# EXT_ADIN.net
KiCad netlist of a schematic drawn in EAGLE
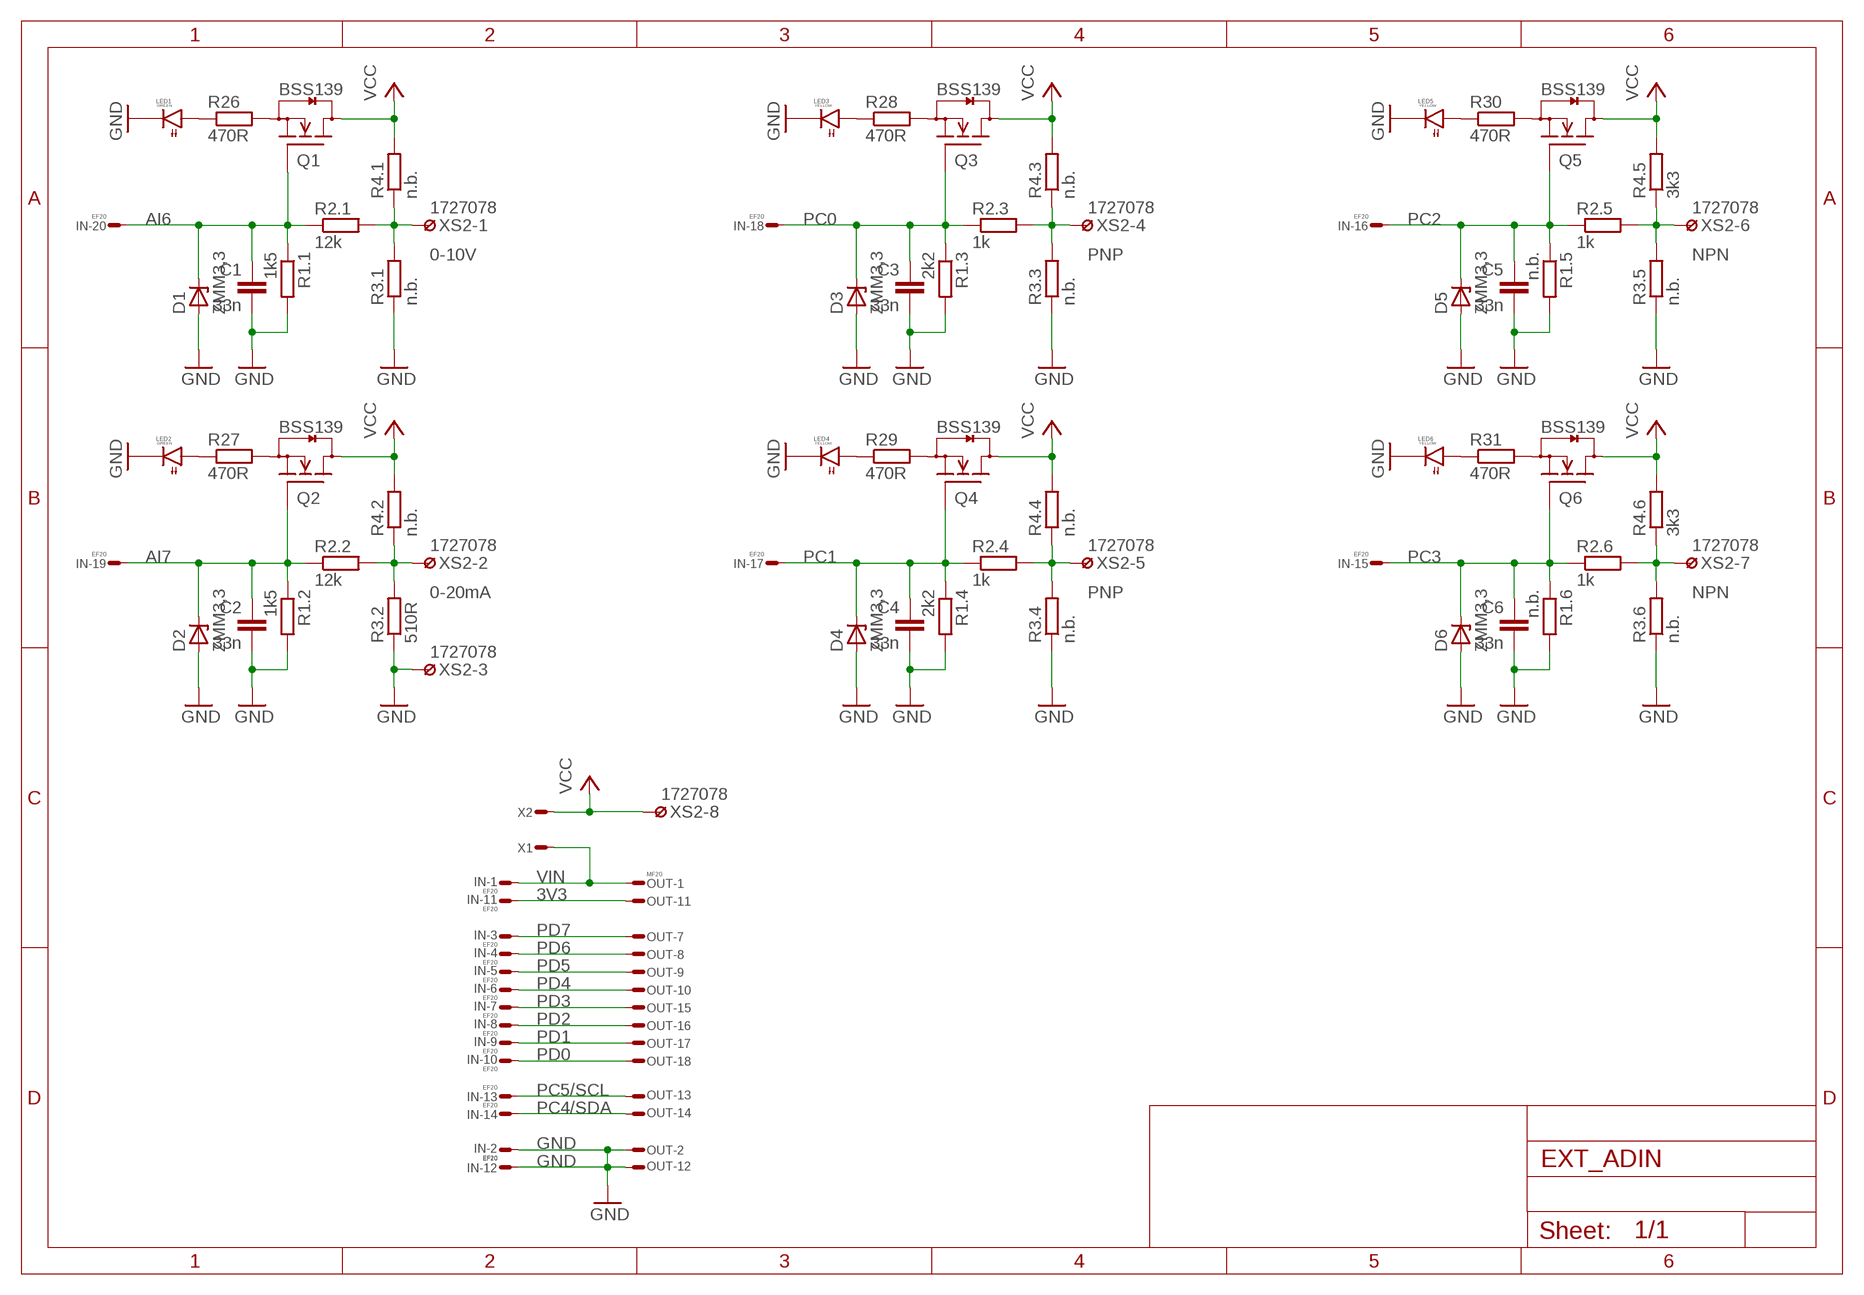
[diagram p0: schematic, sheet 1]

(export (version "E")
  (design (tool "Eeschema 10.0.6"))
  (components
    (comp (ref "C1")
      (value "33n")
      (footprint "eagle-import:1206")
      (libsource (lib "eagle-import") (part "C1206"))
    )
    (comp (ref "C2")
      (value "33n")
      (footprint "eagle-import:1206")
      (libsource (lib "eagle-import") (part "C1206"))
    )
    (comp (ref "C3")
      (value "33n")
      (footprint "eagle-import:1206")
      (libsource (lib "eagle-import") (part "C1206"))
    )
    (comp (ref "C4")
      (value "33n")
      (footprint "eagle-import:1206")
      (libsource (lib "eagle-import") (part "C1206"))
    )
    (comp (ref "C5")
      (value "33n")
      (footprint "eagle-import:1206")
      (libsource (lib "eagle-import") (part "C1206"))
    )
    (comp (ref "C6")
      (value "33n")
      (footprint "eagle-import:1206")
      (libsource (lib "eagle-import") (part "C1206"))
    )
    (comp (ref "D1")
      (value "ZMM3,3")
      (footprint "eagle-import:SOD80")
      (libsource (lib "eagle-import") (part "ZDSOD80"))
    )
    (comp (ref "D2")
      (value "ZMM3,3")
      (footprint "eagle-import:SOD80")
      (libsource (lib "eagle-import") (part "ZDSOD80"))
    )
    (comp (ref "D3")
      (value "ZMM3,3")
      (footprint "eagle-import:SOD80")
      (libsource (lib "eagle-import") (part "ZDSOD80"))
    )
    (comp (ref "D4")
      (value "ZMM3,3")
      (footprint "eagle-import:SOD80")
      (libsource (lib "eagle-import") (part "ZDSOD80"))
    )
    (comp (ref "D5")
      (value "ZMM3,3")
      (footprint "eagle-import:SOD80")
      (libsource (lib "eagle-import") (part "ZDSOD80"))
    )
    (comp (ref "D6")
      (value "ZMM3,3")
      (footprint "eagle-import:SOD80")
      (libsource (lib "eagle-import") (part "ZDSOD80"))
    )
    (comp (ref "IN")
      (value "EF20")
      (footprint "eagle-import:FE10-2WSS")
      (libsource (lib "eagle-import") (part "FE20ELSS"))
    )
    (comp (ref "LED1")
      (value "GREEN")
      (footprint "eagle-import:1206")
      (libsource (lib "eagle-import") (part "LED1206"))
    )
    (comp (ref "LED2")
      (value "GREEN")
      (footprint "eagle-import:1206")
      (libsource (lib "eagle-import") (part "LED1206"))
    )
    (comp (ref "LED3")
      (value "YELLOW")
      (footprint "eagle-import:1206")
      (libsource (lib "eagle-import") (part "LED1206"))
    )
    (comp (ref "LED4")
      (value "YELLOW")
      (footprint "eagle-import:1206")
      (libsource (lib "eagle-import") (part "LED1206"))
    )
    (comp (ref "LED5")
      (value "YELLOW")
      (footprint "eagle-import:1206")
      (libsource (lib "eagle-import") (part "LED1206"))
    )
    (comp (ref "LED6")
      (value "YELLOW")
      (footprint "eagle-import:1206")
      (libsource (lib "eagle-import") (part "LED1206"))
    )
    (comp (ref "OUT")
      (value "MF20")
      (footprint "eagle-import:ML20LS")
      (libsource (lib "eagle-import") (part "ML20?ELS"))
    )
    (comp (ref "Q1")
      (value "BSS139")
      (footprint "eagle-import:SOT23")
      (libsource (lib "eagle-import") (part "FET-ND23"))
    )
    (comp (ref "Q2")
      (value "BSS139")
      (footprint "eagle-import:SOT23")
      (libsource (lib "eagle-import") (part "FET-ND23"))
    )
    (comp (ref "Q3")
      (value "BSS139")
      (footprint "eagle-import:SOT23")
      (libsource (lib "eagle-import") (part "FET-ND23"))
    )
    (comp (ref "Q4")
      (value "BSS139")
      (footprint "eagle-import:SOT23")
      (libsource (lib "eagle-import") (part "FET-ND23"))
    )
    (comp (ref "Q5")
      (value "BSS139")
      (footprint "eagle-import:SOT23")
      (libsource (lib "eagle-import") (part "FET-ND23"))
    )
    (comp (ref "Q6")
      (value "BSS139")
      (footprint "eagle-import:SOT23")
      (libsource (lib "eagle-import") (part "FET-ND23"))
    )
    (comp (ref "R1.1")
      (value "1k5")
      (footprint "eagle-import:1206")
      (libsource (lib "eagle-import") (part "R1206"))
    )
    (comp (ref "R1.2")
      (value "1k5")
      (footprint "eagle-import:1206")
      (libsource (lib "eagle-import") (part "R1206"))
    )
    (comp (ref "R1.3")
      (value "2k2")
      (footprint "eagle-import:1206")
      (libsource (lib "eagle-import") (part "R1206"))
    )
    (comp (ref "R1.4")
      (value "2k2")
      (footprint "eagle-import:1206")
      (libsource (lib "eagle-import") (part "R1206"))
    )
    (comp (ref "R1.5")
      (value "n.b.")
      (footprint "eagle-import:1206")
      (libsource (lib "eagle-import") (part "R1206"))
    )
    (comp (ref "R1.6")
      (value "n.b.")
      (footprint "eagle-import:1206")
      (libsource (lib "eagle-import") (part "R1206"))
    )
    (comp (ref "R2.1")
      (value "12k")
      (footprint "eagle-import:1206")
      (libsource (lib "eagle-import") (part "R1206"))
    )
    (comp (ref "R2.2")
      (value "12k")
      (footprint "eagle-import:1206")
      (libsource (lib "eagle-import") (part "R1206"))
    )
    (comp (ref "R2.3")
      (value "1k")
      (footprint "eagle-import:1206")
      (libsource (lib "eagle-import") (part "R1206"))
    )
    (comp (ref "R2.4")
      (value "1k")
      (footprint "eagle-import:1206")
      (libsource (lib "eagle-import") (part "R1206"))
    )
    (comp (ref "R2.5")
      (value "1k")
      (footprint "eagle-import:1206")
      (libsource (lib "eagle-import") (part "R1206"))
    )
    (comp (ref "R2.6")
      (value "1k")
      (footprint "eagle-import:1206")
      (libsource (lib "eagle-import") (part "R1206"))
    )
    (comp (ref "R3.1")
      (value "n.b.")
      (footprint "eagle-import:1206")
      (libsource (lib "eagle-import") (part "R1206"))
    )
    (comp (ref "R3.2")
      (value "510R")
      (footprint "eagle-import:1206")
      (libsource (lib "eagle-import") (part "R1206"))
    )
    (comp (ref "R3.3")
      (value "n.b.")
      (footprint "eagle-import:1206")
      (libsource (lib "eagle-import") (part "R1206"))
    )
    (comp (ref "R3.4")
      (value "n.b.")
      (footprint "eagle-import:1206")
      (libsource (lib "eagle-import") (part "R1206"))
    )
    (comp (ref "R3.5")
      (value "n.b.")
      (footprint "eagle-import:1206")
      (libsource (lib "eagle-import") (part "R1206"))
    )
    (comp (ref "R3.6")
      (value "n.b.")
      (footprint "eagle-import:1206")
      (libsource (lib "eagle-import") (part "R1206"))
    )
    (comp (ref "R4.1")
      (value "n.b.")
      (footprint "eagle-import:1206")
      (libsource (lib "eagle-import") (part "R1206"))
    )
    (comp (ref "R4.2")
      (value "n.b.")
      (footprint "eagle-import:1206")
      (libsource (lib "eagle-import") (part "R1206"))
    )
    (comp (ref "R4.3")
      (value "n.b.")
      (footprint "eagle-import:1206")
      (libsource (lib "eagle-import") (part "R1206"))
    )
    (comp (ref "R4.4")
      (value "n.b.")
      (footprint "eagle-import:1206")
      (libsource (lib "eagle-import") (part "R1206"))
    )
    (comp (ref "R4.5")
      (value "3k3")
      (footprint "eagle-import:1206")
      (libsource (lib "eagle-import") (part "R1206"))
    )
    (comp (ref "R4.6")
      (value "3k3")
      (footprint "eagle-import:1206")
      (libsource (lib "eagle-import") (part "R1206"))
    )
    (comp (ref "R26")
      (value "470R")
      (footprint "eagle-import:1206")
      (libsource (lib "eagle-import") (part "R1206"))
    )
    (comp (ref "R27")
      (value "470R")
      (footprint "eagle-import:1206")
      (libsource (lib "eagle-import") (part "R1206"))
    )
    (comp (ref "R28")
      (value "470R")
      (footprint "eagle-import:1206")
      (libsource (lib "eagle-import") (part "R1206"))
    )
    (comp (ref "R29")
      (value "470R")
      (footprint "eagle-import:1206")
      (libsource (lib "eagle-import") (part "R1206"))
    )
    (comp (ref "R30")
      (value "470R")
      (footprint "eagle-import:1206")
      (libsource (lib "eagle-import") (part "R1206"))
    )
    (comp (ref "R31")
      (value "470R")
      (footprint "eagle-import:1206")
      (libsource (lib "eagle-import") (part "R1206"))
    )
    (comp (ref "X1")
      (value "WIREPADT1.6/0.9")
      (footprint "eagle-import:T1.6_0.9")
      (libsource (lib "eagle-import") (part "WIREPADT1.6/0.9"))
    )
    (comp (ref "X2")
      (value "WIREPADT1.6/0.9")
      (footprint "eagle-import:T1.6_0.9")
      (libsource (lib "eagle-import") (part "WIREPADT1.6/0.9"))
    )
    (comp (ref "XS2")
      (value "1727078")
      (footprint "eagle-import:1727078")
      (libsource (lib "eagle-import") (part "CON8-SS381"))
    )
  )
  (nets
    (net (code "1") (name "/3V3") (class "Default")
      (node (ref "IN") (pin "P$11") (pinfunction "S_P$11") (pintype "passive"))
      (node (ref "OUT") (pin "P$11") (pinfunction "S_P$11") (pintype "passive"))
    )
    (net (code "2") (name "/AI6") (class "Default")
      (node (ref "C1") (pin "1") (pinfunction "1_1") (pintype "passive"))
      (node (ref "D1") (pin "C") (pinfunction "C_C") (pintype "passive"))
      (node (ref "IN") (pin "P$20") (pinfunction "S_P$20") (pintype "passive"))
      (node (ref "Q1") (pin "1") (pinfunction "G_1") (pintype "passive"))
      (node (ref "R1.1") (pin "1") (pinfunction "1_1") (pintype "passive"))
      (node (ref "R2.1") (pin "1") (pinfunction "1_1") (pintype "passive"))
    )
    (net (code "3") (name "/AI7") (class "Default")
      (node (ref "C2") (pin "1") (pinfunction "1_1") (pintype "passive"))
      (node (ref "D2") (pin "C") (pinfunction "C_C") (pintype "passive"))
      (node (ref "IN") (pin "P$19") (pinfunction "S_P$19") (pintype "passive"))
      (node (ref "Q2") (pin "1") (pinfunction "G_1") (pintype "passive"))
      (node (ref "R1.2") (pin "1") (pinfunction "1_1") (pintype "passive"))
      (node (ref "R2.2") (pin "1") (pinfunction "1_1") (pintype "passive"))
    )
    (net (code "4") (name "/PC0") (class "Default")
      (node (ref "C3") (pin "1") (pinfunction "1_1") (pintype "passive"))
      (node (ref "D3") (pin "C") (pinfunction "C_C") (pintype "passive"))
      (node (ref "IN") (pin "P$18") (pinfunction "S_P$18") (pintype "passive"))
      (node (ref "Q3") (pin "1") (pinfunction "G_1") (pintype "passive"))
      (node (ref "R1.3") (pin "1") (pinfunction "1_1") (pintype "passive"))
      (node (ref "R2.3") (pin "1") (pinfunction "1_1") (pintype "passive"))
    )
    (net (code "5") (name "/PC1") (class "Default")
      (node (ref "C4") (pin "1") (pinfunction "1_1") (pintype "passive"))
      (node (ref "D4") (pin "C") (pinfunction "C_C") (pintype "passive"))
      (node (ref "IN") (pin "P$17") (pinfunction "S_P$17") (pintype "passive"))
      (node (ref "Q4") (pin "1") (pinfunction "G_1") (pintype "passive"))
      (node (ref "R1.4") (pin "1") (pinfunction "1_1") (pintype "passive"))
      (node (ref "R2.4") (pin "1") (pinfunction "1_1") (pintype "passive"))
    )
    (net (code "6") (name "/PC2") (class "Default")
      (node (ref "C5") (pin "1") (pinfunction "1_1") (pintype "passive"))
      (node (ref "D5") (pin "C") (pinfunction "C_C") (pintype "passive"))
      (node (ref "IN") (pin "P$16") (pinfunction "S_P$16") (pintype "passive"))
      (node (ref "Q5") (pin "1") (pinfunction "G_1") (pintype "passive"))
      (node (ref "R1.5") (pin "1") (pinfunction "1_1") (pintype "passive"))
      (node (ref "R2.5") (pin "1") (pinfunction "1_1") (pintype "passive"))
    )
    (net (code "7") (name "/PC3") (class "Default")
      (node (ref "C6") (pin "1") (pinfunction "1_1") (pintype "passive"))
      (node (ref "D6") (pin "C") (pinfunction "C_C") (pintype "passive"))
      (node (ref "IN") (pin "P$15") (pinfunction "S_P$15") (pintype "passive"))
      (node (ref "Q6") (pin "1") (pinfunction "G_1") (pintype "passive"))
      (node (ref "R1.6") (pin "1") (pinfunction "1_1") (pintype "passive"))
      (node (ref "R2.6") (pin "1") (pinfunction "1_1") (pintype "passive"))
    )
    (net (code "8") (name "/PC4{slash}SDA") (class "Default")
      (node (ref "IN") (pin "P$14") (pinfunction "S_P$14") (pintype "passive"))
      (node (ref "OUT") (pin "P$14") (pinfunction "S_P$14") (pintype "passive"))
    )
    (net (code "9") (name "/PC5{slash}SCL") (class "Default")
      (node (ref "IN") (pin "P$13") (pinfunction "S_P$13") (pintype "passive"))
      (node (ref "OUT") (pin "P$13") (pinfunction "S_P$13") (pintype "passive"))
    )
    (net (code "10") (name "/PD0") (class "Default")
      (node (ref "IN") (pin "P$10") (pinfunction "S_P$10") (pintype "passive"))
      (node (ref "OUT") (pin "P$18") (pinfunction "S_P$18") (pintype "passive"))
    )
    (net (code "11") (name "/PD1") (class "Default")
      (node (ref "IN") (pin "P$9") (pinfunction "S_P$9") (pintype "passive"))
      (node (ref "OUT") (pin "P$17") (pinfunction "S_P$17") (pintype "passive"))
    )
    (net (code "12") (name "/PD2") (class "Default")
      (node (ref "IN") (pin "P$8") (pinfunction "S_P$8") (pintype "passive"))
      (node (ref "OUT") (pin "P$16") (pinfunction "S_P$16") (pintype "passive"))
    )
    (net (code "13") (name "/PD3") (class "Default")
      (node (ref "IN") (pin "P$7") (pinfunction "S_P$7") (pintype "passive"))
      (node (ref "OUT") (pin "P$15") (pinfunction "S_P$15") (pintype "passive"))
    )
    (net (code "14") (name "/PD4") (class "Default")
      (node (ref "IN") (pin "P$6") (pinfunction "S_P$6") (pintype "passive"))
      (node (ref "OUT") (pin "P$10") (pinfunction "S_P$10") (pintype "passive"))
    )
    (net (code "15") (name "/PD5") (class "Default")
      (node (ref "IN") (pin "P$5") (pinfunction "S_P$5") (pintype "passive"))
      (node (ref "OUT") (pin "P$9") (pinfunction "S_P$9") (pintype "passive"))
    )
    (net (code "16") (name "/PD6") (class "Default")
      (node (ref "IN") (pin "P$4") (pinfunction "S_P$4") (pintype "passive"))
      (node (ref "OUT") (pin "P$8") (pinfunction "S_P$8") (pintype "passive"))
    )
    (net (code "17") (name "/PD7") (class "Default")
      (node (ref "IN") (pin "P$3") (pinfunction "S_P$3") (pintype "passive"))
      (node (ref "OUT") (pin "P$7") (pinfunction "S_P$7") (pintype "passive"))
    )
    (net (code "18") (name "/VIN") (class "Default")
      (node (ref "IN") (pin "P$1") (pinfunction "S_P$1") (pintype "passive"))
      (node (ref "OUT") (pin "P$1") (pinfunction "S_P$1") (pintype "passive"))
      (node (ref "X1") (pin "1") (pinfunction "S_1") (pintype "passive"))
    )
    (net (code "19") (name "GND") (class "Default")
      (node (ref "C1") (pin "2") (pinfunction "2_2") (pintype "passive"))
      (node (ref "C2") (pin "2") (pinfunction "2_2") (pintype "passive"))
      (node (ref "C3") (pin "2") (pinfunction "2_2") (pintype "passive"))
      (node (ref "C4") (pin "2") (pinfunction "2_2") (pintype "passive"))
      (node (ref "C5") (pin "2") (pinfunction "2_2") (pintype "passive"))
      (node (ref "C6") (pin "2") (pinfunction "2_2") (pintype "passive"))
      (node (ref "D1") (pin "A") (pinfunction "A_A") (pintype "passive"))
      (node (ref "D2") (pin "A") (pinfunction "A_A") (pintype "passive"))
      (node (ref "D3") (pin "A") (pinfunction "A_A") (pintype "passive"))
      (node (ref "D4") (pin "A") (pinfunction "A_A") (pintype "passive"))
      (node (ref "D5") (pin "A") (pinfunction "A_A") (pintype "passive"))
      (node (ref "D6") (pin "A") (pinfunction "A_A") (pintype "passive"))
      (node (ref "IN") (pin "P$12") (pinfunction "S_P$12") (pintype "passive"))
      (node (ref "IN") (pin "P$2") (pinfunction "S_P$2") (pintype "passive"))
      (node (ref "LED1") (pin "2") (pinfunction "C_2") (pintype "bidirectional"))
      (node (ref "LED2") (pin "2") (pinfunction "C_2") (pintype "bidirectional"))
      (node (ref "LED3") (pin "2") (pinfunction "C_2") (pintype "bidirectional"))
      (node (ref "LED4") (pin "2") (pinfunction "C_2") (pintype "bidirectional"))
      (node (ref "LED5") (pin "2") (pinfunction "C_2") (pintype "bidirectional"))
      (node (ref "LED6") (pin "2") (pinfunction "C_2") (pintype "bidirectional"))
      (node (ref "OUT") (pin "P$12") (pinfunction "S_P$12") (pintype "passive"))
      (node (ref "OUT") (pin "P$2") (pinfunction "S_P$2") (pintype "passive"))
      (node (ref "R1.1") (pin "2") (pinfunction "2_2") (pintype "passive"))
      (node (ref "R1.2") (pin "2") (pinfunction "2_2") (pintype "passive"))
      (node (ref "R1.3") (pin "2") (pinfunction "2_2") (pintype "passive"))
      (node (ref "R1.4") (pin "2") (pinfunction "2_2") (pintype "passive"))
      (node (ref "R1.5") (pin "2") (pinfunction "2_2") (pintype "passive"))
      (node (ref "R1.6") (pin "2") (pinfunction "2_2") (pintype "passive"))
      (node (ref "R3.1") (pin "1") (pinfunction "1_1") (pintype "passive"))
      (node (ref "R3.2") (pin "1") (pinfunction "1_1") (pintype "passive"))
      (node (ref "R3.3") (pin "1") (pinfunction "1_1") (pintype "passive"))
      (node (ref "R3.4") (pin "1") (pinfunction "1_1") (pintype "passive"))
      (node (ref "R3.5") (pin "1") (pinfunction "1_1") (pintype "passive"))
      (node (ref "R3.6") (pin "1") (pinfunction "1_1") (pintype "passive"))
      (node (ref "XS2") (pin "P$3") (pinfunction "K_P$3") (pintype "passive"))
    )
    (net (code "20") (name "Net-(LED1-A)") (class "Default")
      (node (ref "LED1") (pin "1") (pinfunction "A_1") (pintype "bidirectional"))
      (node (ref "R26") (pin "1") (pinfunction "1_1") (pintype "passive"))
    )
    (net (code "21") (name "Net-(LED2-A)") (class "Default")
      (node (ref "LED2") (pin "1") (pinfunction "A_1") (pintype "bidirectional"))
      (node (ref "R27") (pin "1") (pinfunction "1_1") (pintype "passive"))
    )
    (net (code "22") (name "Net-(LED3-A)") (class "Default")
      (node (ref "LED3") (pin "1") (pinfunction "A_1") (pintype "bidirectional"))
      (node (ref "R28") (pin "1") (pinfunction "1_1") (pintype "passive"))
    )
    (net (code "23") (name "Net-(LED4-A)") (class "Default")
      (node (ref "LED4") (pin "1") (pinfunction "A_1") (pintype "bidirectional"))
      (node (ref "R29") (pin "1") (pinfunction "1_1") (pintype "passive"))
    )
    (net (code "24") (name "Net-(LED5-A)") (class "Default")
      (node (ref "LED5") (pin "1") (pinfunction "A_1") (pintype "bidirectional"))
      (node (ref "R30") (pin "1") (pinfunction "1_1") (pintype "passive"))
    )
    (net (code "25") (name "Net-(LED6-A)") (class "Default")
      (node (ref "LED6") (pin "1") (pinfunction "A_1") (pintype "bidirectional"))
      (node (ref "R31") (pin "1") (pinfunction "1_1") (pintype "passive"))
    )
    (net (code "26") (name "Net-(Q1-S)") (class "Default")
      (node (ref "Q1") (pin "2") (pinfunction "S_2") (pintype "passive"))
      (node (ref "R26") (pin "2") (pinfunction "2_2") (pintype "passive"))
    )
    (net (code "27") (name "Net-(Q2-S)") (class "Default")
      (node (ref "Q2") (pin "2") (pinfunction "S_2") (pintype "passive"))
      (node (ref "R27") (pin "2") (pinfunction "2_2") (pintype "passive"))
    )
    (net (code "28") (name "Net-(Q3-S)") (class "Default")
      (node (ref "Q3") (pin "2") (pinfunction "S_2") (pintype "passive"))
      (node (ref "R28") (pin "2") (pinfunction "2_2") (pintype "passive"))
    )
    (net (code "29") (name "Net-(Q4-S)") (class "Default")
      (node (ref "Q4") (pin "2") (pinfunction "S_2") (pintype "passive"))
      (node (ref "R29") (pin "2") (pinfunction "2_2") (pintype "passive"))
    )
    (net (code "30") (name "Net-(Q5-S)") (class "Default")
      (node (ref "Q5") (pin "2") (pinfunction "S_2") (pintype "passive"))
      (node (ref "R30") (pin "2") (pinfunction "2_2") (pintype "passive"))
    )
    (net (code "31") (name "Net-(Q6-S)") (class "Default")
      (node (ref "Q6") (pin "2") (pinfunction "S_2") (pintype "passive"))
      (node (ref "R31") (pin "2") (pinfunction "2_2") (pintype "passive"))
    )
    (net (code "32") (name "Net-(XS2A-K)") (class "Default")
      (node (ref "R2.1") (pin "2") (pinfunction "2_2") (pintype "passive"))
      (node (ref "R3.1") (pin "2") (pinfunction "2_2") (pintype "passive"))
      (node (ref "R4.1") (pin "1") (pinfunction "1_1") (pintype "passive"))
      (node (ref "XS2") (pin "P$1") (pinfunction "K_P$1") (pintype "passive"))
    )
    (net (code "33") (name "Net-(XS2B-K)") (class "Default")
      (node (ref "R2.2") (pin "2") (pinfunction "2_2") (pintype "passive"))
      (node (ref "R3.2") (pin "2") (pinfunction "2_2") (pintype "passive"))
      (node (ref "R4.2") (pin "1") (pinfunction "1_1") (pintype "passive"))
      (node (ref "XS2") (pin "P$2") (pinfunction "K_P$2") (pintype "passive"))
    )
    (net (code "34") (name "Net-(XS2D-K)") (class "Default")
      (node (ref "R2.3") (pin "2") (pinfunction "2_2") (pintype "passive"))
      (node (ref "R3.3") (pin "2") (pinfunction "2_2") (pintype "passive"))
      (node (ref "R4.3") (pin "1") (pinfunction "1_1") (pintype "passive"))
      (node (ref "XS2") (pin "P$4") (pinfunction "K_P$4") (pintype "passive"))
    )
    (net (code "35") (name "Net-(XS2E-K)") (class "Default")
      (node (ref "R2.4") (pin "2") (pinfunction "2_2") (pintype "passive"))
      (node (ref "R3.4") (pin "2") (pinfunction "2_2") (pintype "passive"))
      (node (ref "R4.4") (pin "1") (pinfunction "1_1") (pintype "passive"))
      (node (ref "XS2") (pin "P$5") (pinfunction "K_P$5") (pintype "passive"))
    )
    (net (code "36") (name "Net-(XS2F-K)") (class "Default")
      (node (ref "R2.5") (pin "2") (pinfunction "2_2") (pintype "passive"))
      (node (ref "R3.5") (pin "2") (pinfunction "2_2") (pintype "passive"))
      (node (ref "R4.5") (pin "1") (pinfunction "1_1") (pintype "passive"))
      (node (ref "XS2") (pin "P$6") (pinfunction "K_P$6") (pintype "passive"))
    )
    (net (code "37") (name "Net-(XS2G-K)") (class "Default")
      (node (ref "R2.6") (pin "2") (pinfunction "2_2") (pintype "passive"))
      (node (ref "R3.6") (pin "2") (pinfunction "2_2") (pintype "passive"))
      (node (ref "R4.6") (pin "1") (pinfunction "1_1") (pintype "passive"))
      (node (ref "XS2") (pin "P$7") (pinfunction "K_P$7") (pintype "passive"))
    )
    (net (code "38") (name "VCC") (class "Default")
      (node (ref "Q1") (pin "3") (pinfunction "D_3") (pintype "passive"))
      (node (ref "Q2") (pin "3") (pinfunction "D_3") (pintype "passive"))
      (node (ref "Q3") (pin "3") (pinfunction "D_3") (pintype "passive"))
      (node (ref "Q4") (pin "3") (pinfunction "D_3") (pintype "passive"))
      (node (ref "Q5") (pin "3") (pinfunction "D_3") (pintype "passive"))
      (node (ref "Q6") (pin "3") (pinfunction "D_3") (pintype "passive"))
      (node (ref "R4.1") (pin "2") (pinfunction "2_2") (pintype "passive"))
      (node (ref "R4.2") (pin "2") (pinfunction "2_2") (pintype "passive"))
      (node (ref "R4.3") (pin "2") (pinfunction "2_2") (pintype "passive"))
      (node (ref "R4.4") (pin "2") (pinfunction "2_2") (pintype "passive"))
      (node (ref "R4.5") (pin "2") (pinfunction "2_2") (pintype "passive"))
      (node (ref "R4.6") (pin "2") (pinfunction "2_2") (pintype "passive"))
      (node (ref "X2") (pin "1") (pinfunction "S_1") (pintype "passive"))
      (node (ref "XS2") (pin "P$8") (pinfunction "K_P$8") (pintype "passive"))
    )
  )
)
